# LED_s_Valvulas.net
KiCad netlist of a schematic drawn in Altium Designer
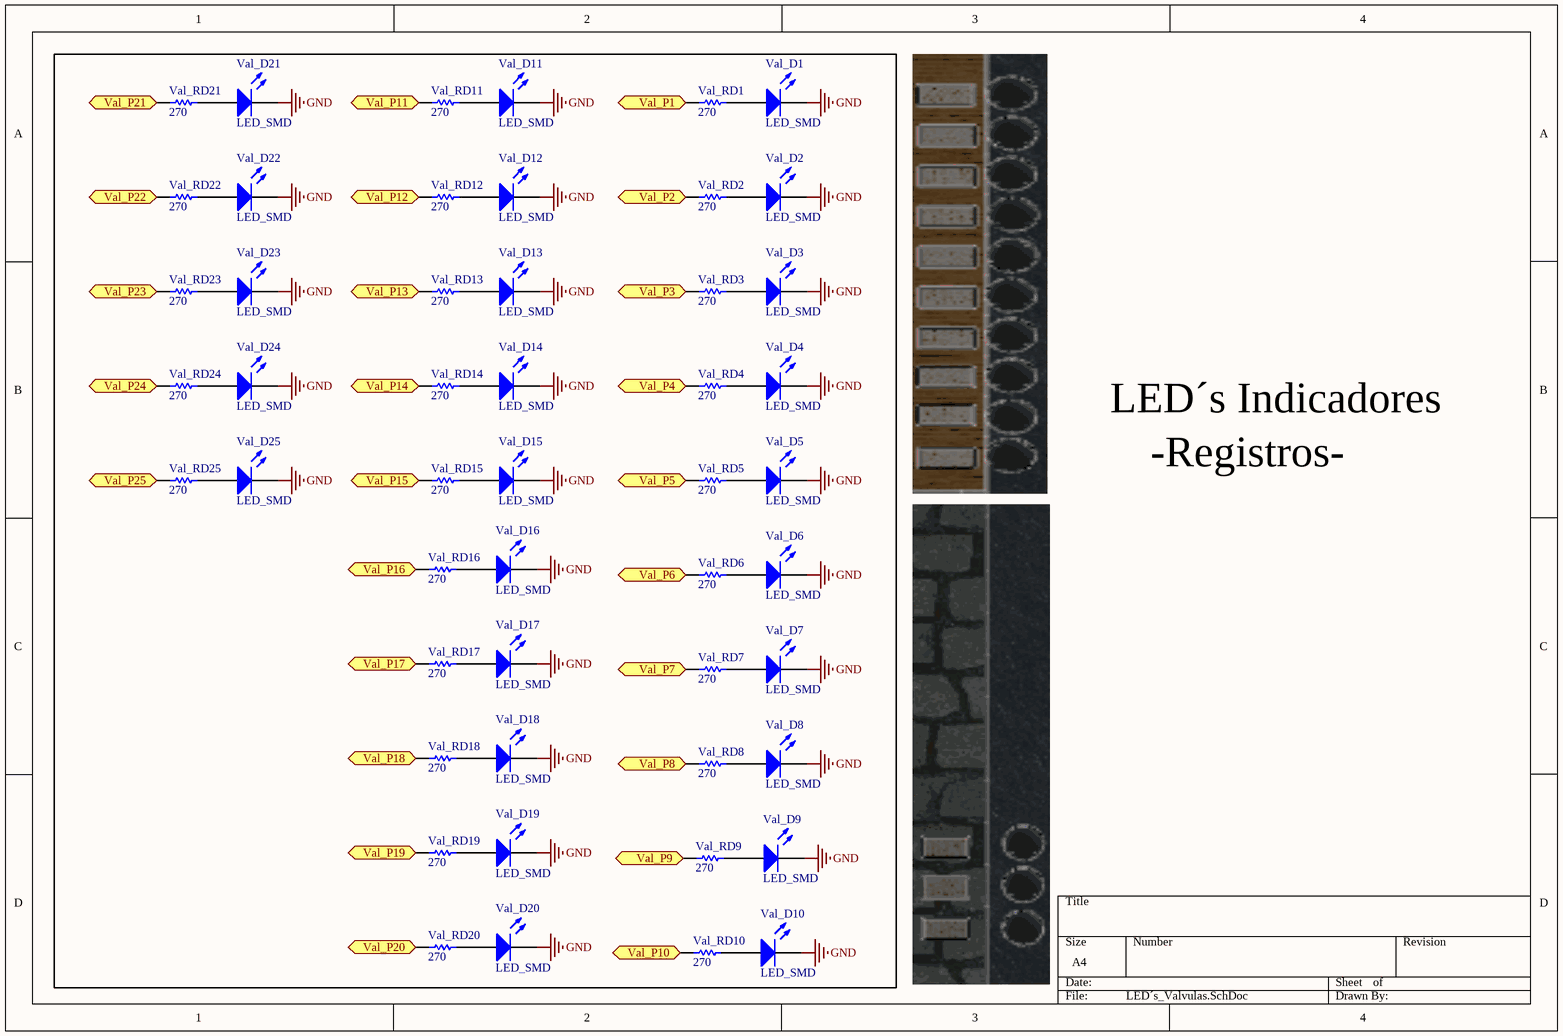
[diagram p0: LED´s_Valvulas.SchDoc]

(export (version "E")
  (design (tool "Eeschema 10.0.6"))
  (components
    (comp (ref "Val_D1")
      (value "LED_SMD")
      (footprint "0805")
      (description "LED SMD")
      (fields (field (name "PUBLISHER") "Altium Limited"))
      (libsource (lib "Libreria_Organo") (part "LED_SMD"))
    )
    (comp (ref "Val_D2")
      (value "LED_SMD")
      (footprint "0805")
      (description "LED SMD")
      (fields (field (name "PUBLISHER") "Altium Limited"))
      (libsource (lib "Libreria_Organo") (part "LED_SMD"))
    )
    (comp (ref "Val_D3")
      (value "LED_SMD")
      (footprint "0805")
      (description "LED SMD")
      (fields (field (name "PUBLISHER") "Altium Limited"))
      (libsource (lib "Libreria_Organo") (part "LED_SMD"))
    )
    (comp (ref "Val_D4")
      (value "LED_SMD")
      (footprint "0805")
      (description "LED SMD")
      (fields (field (name "PUBLISHER") "Altium Limited"))
      (libsource (lib "Libreria_Organo") (part "LED_SMD"))
    )
    (comp (ref "Val_D5")
      (value "LED_SMD")
      (footprint "0805")
      (description "LED SMD")
      (fields (field (name "PUBLISHER") "Altium Limited"))
      (libsource (lib "Libreria_Organo") (part "LED_SMD"))
    )
    (comp (ref "Val_D6")
      (value "LED_SMD")
      (footprint "0805")
      (description "LED SMD")
      (fields (field (name "PUBLISHER") "Altium Limited"))
      (libsource (lib "Libreria_Organo") (part "LED_SMD"))
    )
    (comp (ref "Val_D7")
      (value "LED_SMD")
      (footprint "0805")
      (description "LED SMD")
      (fields (field (name "PUBLISHER") "Altium Limited"))
      (libsource (lib "Libreria_Organo") (part "LED_SMD"))
    )
    (comp (ref "Val_D8")
      (value "LED_SMD")
      (footprint "0805")
      (description "LED SMD")
      (fields (field (name "PUBLISHER") "Altium Limited"))
      (libsource (lib "Libreria_Organo") (part "LED_SMD"))
    )
    (comp (ref "Val_D9")
      (value "LED_SMD")
      (footprint "0805")
      (description "LED SMD")
      (fields (field (name "PUBLISHER") "Altium Limited"))
      (libsource (lib "Libreria_Organo") (part "LED_SMD"))
    )
    (comp (ref "Val_D10")
      (value "LED_SMD")
      (footprint "0805")
      (description "LED SMD")
      (fields (field (name "PUBLISHER") "Altium Limited"))
      (libsource (lib "Libreria_Organo") (part "LED_SMD"))
    )
    (comp (ref "Val_D11")
      (value "LED_SMD")
      (footprint "0805")
      (description "LED SMD")
      (fields (field (name "PUBLISHER") "Altium Limited"))
      (libsource (lib "Libreria_Organo") (part "LED_SMD"))
    )
    (comp (ref "Val_D12")
      (value "LED_SMD")
      (footprint "0805")
      (description "LED SMD")
      (fields (field (name "PUBLISHER") "Altium Limited"))
      (libsource (lib "Libreria_Organo") (part "LED_SMD"))
    )
    (comp (ref "Val_D13")
      (value "LED_SMD")
      (footprint "0805")
      (description "LED SMD")
      (fields (field (name "PUBLISHER") "Altium Limited"))
      (libsource (lib "Libreria_Organo") (part "LED_SMD"))
    )
    (comp (ref "Val_D14")
      (value "LED_SMD")
      (footprint "0805")
      (description "LED SMD")
      (fields (field (name "PUBLISHER") "Altium Limited"))
      (libsource (lib "Libreria_Organo") (part "LED_SMD"))
    )
    (comp (ref "Val_D15")
      (value "LED_SMD")
      (footprint "0805")
      (description "LED SMD")
      (fields (field (name "PUBLISHER") "Altium Limited"))
      (libsource (lib "Libreria_Organo") (part "LED_SMD"))
    )
    (comp (ref "Val_D16")
      (value "LED_SMD")
      (footprint "0805")
      (description "LED SMD")
      (fields (field (name "PUBLISHER") "Altium Limited"))
      (libsource (lib "Libreria_Organo") (part "LED_SMD"))
    )
    (comp (ref "Val_D17")
      (value "LED_SMD")
      (footprint "0805")
      (description "LED SMD")
      (fields (field (name "PUBLISHER") "Altium Limited"))
      (libsource (lib "Libreria_Organo") (part "LED_SMD"))
    )
    (comp (ref "Val_D18")
      (value "LED_SMD")
      (footprint "0805")
      (description "LED SMD")
      (fields (field (name "PUBLISHER") "Altium Limited"))
      (libsource (lib "Libreria_Organo") (part "LED_SMD"))
    )
    (comp (ref "Val_D19")
      (value "LED_SMD")
      (footprint "0805")
      (description "LED SMD")
      (fields (field (name "PUBLISHER") "Altium Limited"))
      (libsource (lib "Libreria_Organo") (part "LED_SMD"))
    )
    (comp (ref "Val_D20")
      (value "LED_SMD")
      (footprint "0805")
      (description "LED SMD")
      (fields (field (name "PUBLISHER") "Altium Limited"))
      (libsource (lib "Libreria_Organo") (part "LED_SMD"))
    )
    (comp (ref "Val_D21")
      (value "LED_SMD")
      (footprint "0805")
      (description "LED SMD")
      (fields (field (name "PUBLISHER") "Altium Limited"))
      (libsource (lib "Libreria_Organo") (part "LED_SMD"))
    )
    (comp (ref "Val_D22")
      (value "LED_SMD")
      (footprint "0805")
      (description "LED SMD")
      (fields (field (name "PUBLISHER") "Altium Limited"))
      (libsource (lib "Libreria_Organo") (part "LED_SMD"))
    )
    (comp (ref "Val_D23")
      (value "LED_SMD")
      (footprint "0805")
      (description "LED SMD")
      (fields (field (name "PUBLISHER") "Altium Limited"))
      (libsource (lib "Libreria_Organo") (part "LED_SMD"))
    )
    (comp (ref "Val_D24")
      (value "LED_SMD")
      (footprint "0805")
      (description "LED SMD")
      (fields (field (name "PUBLISHER") "Altium Limited"))
      (libsource (lib "Libreria_Organo") (part "LED_SMD"))
    )
    (comp (ref "Val_D25")
      (value "LED_SMD")
      (footprint "0805")
      (description "LED SMD")
      (fields (field (name "PUBLISHER") "Altium Limited"))
      (libsource (lib "Libreria_Organo") (part "LED_SMD"))
    )
    (comp (ref "Val_RD1")
      (value "270")
      (footprint "0805 Chip Res")
      (description "Res Chip 0805")
      (fields (field (name "PUBLISHER") "Altium Limited"))
      (libsource (lib "Libreria_Organo") (part "Resistencia"))
    )
    (comp (ref "Val_RD2")
      (value "270")
      (footprint "0805 Chip Res")
      (description "Res Chip 0805")
      (fields (field (name "PUBLISHER") "Altium Limited"))
      (libsource (lib "Libreria_Organo") (part "Resistencia"))
    )
    (comp (ref "Val_RD3")
      (value "270")
      (footprint "0805 Chip Res")
      (description "Res Chip 0805")
      (fields (field (name "PUBLISHER") "Altium Limited"))
      (libsource (lib "Libreria_Organo") (part "Resistencia"))
    )
    (comp (ref "Val_RD4")
      (value "270")
      (footprint "0805 Chip Res")
      (description "Res Chip 0805")
      (fields (field (name "PUBLISHER") "Altium Limited"))
      (libsource (lib "Libreria_Organo") (part "Resistencia"))
    )
    (comp (ref "Val_RD5")
      (value "270")
      (footprint "0805 Chip Res")
      (description "Res Chip 0805")
      (fields (field (name "PUBLISHER") "Altium Limited"))
      (libsource (lib "Libreria_Organo") (part "Resistencia"))
    )
    (comp (ref "Val_RD6")
      (value "270")
      (footprint "0805 Chip Res")
      (description "Res Chip 0805")
      (fields (field (name "PUBLISHER") "Altium Limited"))
      (libsource (lib "Libreria_Organo") (part "Resistencia"))
    )
    (comp (ref "Val_RD7")
      (value "270")
      (footprint "0805 Chip Res")
      (description "Res Chip 0805")
      (fields (field (name "PUBLISHER") "Altium Limited"))
      (libsource (lib "Libreria_Organo") (part "Resistencia"))
    )
    (comp (ref "Val_RD8")
      (value "270")
      (footprint "0805 Chip Res")
      (description "Res Chip 0805")
      (fields (field (name "PUBLISHER") "Altium Limited"))
      (libsource (lib "Libreria_Organo") (part "Resistencia"))
    )
    (comp (ref "Val_RD9")
      (value "270")
      (footprint "0805 Chip Res")
      (description "Res Chip 0805")
      (fields (field (name "PUBLISHER") "Altium Limited"))
      (libsource (lib "Libreria_Organo") (part "Resistencia"))
    )
    (comp (ref "Val_RD10")
      (value "270")
      (footprint "0805 Chip Res")
      (description "Res Chip 0805")
      (fields (field (name "PUBLISHER") "Altium Limited"))
      (libsource (lib "Libreria_Organo") (part "Resistencia"))
    )
    (comp (ref "Val_RD11")
      (value "270")
      (footprint "0805 Chip Res")
      (description "Res Chip 0805")
      (fields (field (name "PUBLISHER") "Altium Limited"))
      (libsource (lib "Libreria_Organo") (part "Resistencia"))
    )
    (comp (ref "Val_RD12")
      (value "270")
      (footprint "0805 Chip Res")
      (description "Res Chip 0805")
      (fields (field (name "PUBLISHER") "Altium Limited"))
      (libsource (lib "Libreria_Organo") (part "Resistencia"))
    )
    (comp (ref "Val_RD13")
      (value "270")
      (footprint "0805 Chip Res")
      (description "Res Chip 0805")
      (fields (field (name "PUBLISHER") "Altium Limited"))
      (libsource (lib "Libreria_Organo") (part "Resistencia"))
    )
    (comp (ref "Val_RD14")
      (value "270")
      (footprint "0805 Chip Res")
      (description "Res Chip 0805")
      (fields (field (name "PUBLISHER") "Altium Limited"))
      (libsource (lib "Libreria_Organo") (part "Resistencia"))
    )
    (comp (ref "Val_RD15")
      (value "270")
      (footprint "0805 Chip Res")
      (description "Res Chip 0805")
      (fields (field (name "PUBLISHER") "Altium Limited"))
      (libsource (lib "Libreria_Organo") (part "Resistencia"))
    )
    (comp (ref "Val_RD16")
      (value "270")
      (footprint "0805 Chip Res")
      (description "Res Chip 0805")
      (fields (field (name "PUBLISHER") "Altium Limited"))
      (libsource (lib "Libreria_Organo") (part "Resistencia"))
    )
    (comp (ref "Val_RD17")
      (value "270")
      (footprint "0805 Chip Res")
      (description "Res Chip 0805")
      (fields (field (name "PUBLISHER") "Altium Limited"))
      (libsource (lib "Libreria_Organo") (part "Resistencia"))
    )
    (comp (ref "Val_RD18")
      (value "270")
      (footprint "0805 Chip Res")
      (description "Res Chip 0805")
      (fields (field (name "PUBLISHER") "Altium Limited"))
      (libsource (lib "Libreria_Organo") (part "Resistencia"))
    )
    (comp (ref "Val_RD19")
      (value "270")
      (footprint "0805 Chip Res")
      (description "Res Chip 0805")
      (fields (field (name "PUBLISHER") "Altium Limited"))
      (libsource (lib "Libreria_Organo") (part "Resistencia"))
    )
    (comp (ref "Val_RD20")
      (value "270")
      (footprint "0805 Chip Res")
      (description "Res Chip 0805")
      (fields (field (name "PUBLISHER") "Altium Limited"))
      (libsource (lib "Libreria_Organo") (part "Resistencia"))
    )
    (comp (ref "Val_RD21")
      (value "270")
      (footprint "0805 Chip Res")
      (description "Res Chip 0805")
      (fields (field (name "PUBLISHER") "Altium Limited"))
      (libsource (lib "Libreria_Organo") (part "Resistencia"))
    )
    (comp (ref "Val_RD22")
      (value "270")
      (footprint "0805 Chip Res")
      (description "Res Chip 0805")
      (fields (field (name "PUBLISHER") "Altium Limited"))
      (libsource (lib "Libreria_Organo") (part "Resistencia"))
    )
    (comp (ref "Val_RD23")
      (value "270")
      (footprint "0805 Chip Res")
      (description "Res Chip 0805")
      (fields (field (name "PUBLISHER") "Altium Limited"))
      (libsource (lib "Libreria_Organo") (part "Resistencia"))
    )
    (comp (ref "Val_RD24")
      (value "270")
      (footprint "0805 Chip Res")
      (description "Res Chip 0805")
      (fields (field (name "PUBLISHER") "Altium Limited"))
      (libsource (lib "Libreria_Organo") (part "Resistencia"))
    )
    (comp (ref "Val_RD25")
      (value "270")
      (footprint "0805 Chip Res")
      (description "Res Chip 0805")
      (fields (field (name "PUBLISHER") "Altium Limited"))
      (libsource (lib "Libreria_Organo") (part "Resistencia"))
    )
  )
  (nets
    (net (code "1") (name "/Val_P1") (class "Default")
      (node (ref "Val_RD1") (pin "1") (pinfunction "1_1") (pintype "passive"))
    )
    (net (code "2") (name "/Val_P2") (class "Default")
      (node (ref "Val_RD2") (pin "1") (pinfunction "1_1") (pintype "passive"))
    )
    (net (code "3") (name "/Val_P3") (class "Default")
      (node (ref "Val_RD3") (pin "1") (pinfunction "1_1") (pintype "passive"))
    )
    (net (code "4") (name "/Val_P4") (class "Default")
      (node (ref "Val_RD4") (pin "1") (pinfunction "1_1") (pintype "passive"))
    )
    (net (code "5") (name "/Val_P5") (class "Default")
      (node (ref "Val_RD5") (pin "1") (pinfunction "1_1") (pintype "passive"))
    )
    (net (code "6") (name "/Val_P6") (class "Default")
      (node (ref "Val_RD6") (pin "1") (pinfunction "1_1") (pintype "passive"))
    )
    (net (code "7") (name "/Val_P7") (class "Default")
      (node (ref "Val_RD7") (pin "1") (pinfunction "1_1") (pintype "passive"))
    )
    (net (code "8") (name "/Val_P8") (class "Default")
      (node (ref "Val_RD8") (pin "1") (pinfunction "1_1") (pintype "passive"))
    )
    (net (code "9") (name "/Val_P9") (class "Default")
      (node (ref "Val_RD9") (pin "1") (pinfunction "1_1") (pintype "passive"))
    )
    (net (code "10") (name "/Val_P10") (class "Default")
      (node (ref "Val_RD10") (pin "1") (pinfunction "1_1") (pintype "passive"))
    )
    (net (code "11") (name "/Val_P11") (class "Default")
      (node (ref "Val_RD11") (pin "1") (pinfunction "1_1") (pintype "passive"))
    )
    (net (code "12") (name "/Val_P12") (class "Default")
      (node (ref "Val_RD12") (pin "1") (pinfunction "1_1") (pintype "passive"))
    )
    (net (code "13") (name "/Val_P13") (class "Default")
      (node (ref "Val_RD13") (pin "1") (pinfunction "1_1") (pintype "passive"))
    )
    (net (code "14") (name "/Val_P14") (class "Default")
      (node (ref "Val_RD14") (pin "1") (pinfunction "1_1") (pintype "passive"))
    )
    (net (code "15") (name "/Val_P15") (class "Default")
      (node (ref "Val_RD15") (pin "1") (pinfunction "1_1") (pintype "passive"))
    )
    (net (code "16") (name "/Val_P16") (class "Default")
      (node (ref "Val_RD16") (pin "1") (pinfunction "1_1") (pintype "passive"))
    )
    (net (code "17") (name "/Val_P17") (class "Default")
      (node (ref "Val_RD17") (pin "1") (pinfunction "1_1") (pintype "passive"))
    )
    (net (code "18") (name "/Val_P18") (class "Default")
      (node (ref "Val_RD18") (pin "1") (pinfunction "1_1") (pintype "passive"))
    )
    (net (code "19") (name "/Val_P19") (class "Default")
      (node (ref "Val_RD19") (pin "1") (pinfunction "1_1") (pintype "passive"))
    )
    (net (code "20") (name "/Val_P20") (class "Default")
      (node (ref "Val_RD20") (pin "1") (pinfunction "1_1") (pintype "passive"))
    )
    (net (code "21") (name "/Val_P21") (class "Default")
      (node (ref "Val_RD21") (pin "1") (pinfunction "1_1") (pintype "passive"))
    )
    (net (code "22") (name "/Val_P22") (class "Default")
      (node (ref "Val_RD22") (pin "1") (pinfunction "1_1") (pintype "passive"))
    )
    (net (code "23") (name "/Val_P23") (class "Default")
      (node (ref "Val_RD23") (pin "1") (pinfunction "1_1") (pintype "passive"))
    )
    (net (code "24") (name "/Val_P24") (class "Default")
      (node (ref "Val_RD24") (pin "1") (pinfunction "1_1") (pintype "passive"))
    )
    (net (code "25") (name "/Val_P25") (class "Default")
      (node (ref "Val_RD25") (pin "1") (pinfunction "1_1") (pintype "passive"))
    )
    (net (code "26") (name "GND") (class "Default")
      (node (ref "Val_D1") (pin "2") (pinfunction "K_2") (pintype "passive"))
      (node (ref "Val_D10") (pin "2") (pinfunction "K_2") (pintype "passive"))
      (node (ref "Val_D11") (pin "2") (pinfunction "K_2") (pintype "passive"))
      (node (ref "Val_D12") (pin "2") (pinfunction "K_2") (pintype "passive"))
      (node (ref "Val_D13") (pin "2") (pinfunction "K_2") (pintype "passive"))
      (node (ref "Val_D14") (pin "2") (pinfunction "K_2") (pintype "passive"))
      (node (ref "Val_D15") (pin "2") (pinfunction "K_2") (pintype "passive"))
      (node (ref "Val_D16") (pin "2") (pinfunction "K_2") (pintype "passive"))
      (node (ref "Val_D17") (pin "2") (pinfunction "K_2") (pintype "passive"))
      (node (ref "Val_D18") (pin "2") (pinfunction "K_2") (pintype "passive"))
      (node (ref "Val_D19") (pin "2") (pinfunction "K_2") (pintype "passive"))
      (node (ref "Val_D2") (pin "2") (pinfunction "K_2") (pintype "passive"))
      (node (ref "Val_D20") (pin "2") (pinfunction "K_2") (pintype "passive"))
      (node (ref "Val_D21") (pin "2") (pinfunction "K_2") (pintype "passive"))
      (node (ref "Val_D22") (pin "2") (pinfunction "K_2") (pintype "passive"))
      (node (ref "Val_D23") (pin "2") (pinfunction "K_2") (pintype "passive"))
      (node (ref "Val_D24") (pin "2") (pinfunction "K_2") (pintype "passive"))
      (node (ref "Val_D25") (pin "2") (pinfunction "K_2") (pintype "passive"))
      (node (ref "Val_D3") (pin "2") (pinfunction "K_2") (pintype "passive"))
      (node (ref "Val_D4") (pin "2") (pinfunction "K_2") (pintype "passive"))
      (node (ref "Val_D5") (pin "2") (pinfunction "K_2") (pintype "passive"))
      (node (ref "Val_D6") (pin "2") (pinfunction "K_2") (pintype "passive"))
      (node (ref "Val_D7") (pin "2") (pinfunction "K_2") (pintype "passive"))
      (node (ref "Val_D8") (pin "2") (pinfunction "K_2") (pintype "passive"))
      (node (ref "Val_D9") (pin "2") (pinfunction "K_2") (pintype "passive"))
    )
    (net (code "27") (name "Net-(Val_D1-A)") (class "Default")
      (node (ref "Val_D1") (pin "1") (pinfunction "A_1") (pintype "passive"))
      (node (ref "Val_RD1") (pin "2") (pinfunction "2_2") (pintype "passive"))
    )
    (net (code "28") (name "Net-(Val_D2-A)") (class "Default")
      (node (ref "Val_D2") (pin "1") (pinfunction "A_1") (pintype "passive"))
      (node (ref "Val_RD2") (pin "2") (pinfunction "2_2") (pintype "passive"))
    )
    (net (code "29") (name "Net-(Val_D3-A)") (class "Default")
      (node (ref "Val_D3") (pin "1") (pinfunction "A_1") (pintype "passive"))
      (node (ref "Val_RD3") (pin "2") (pinfunction "2_2") (pintype "passive"))
    )
    (net (code "30") (name "Net-(Val_D4-A)") (class "Default")
      (node (ref "Val_D4") (pin "1") (pinfunction "A_1") (pintype "passive"))
      (node (ref "Val_RD4") (pin "2") (pinfunction "2_2") (pintype "passive"))
    )
    (net (code "31") (name "Net-(Val_D5-A)") (class "Default")
      (node (ref "Val_D5") (pin "1") (pinfunction "A_1") (pintype "passive"))
      (node (ref "Val_RD5") (pin "2") (pinfunction "2_2") (pintype "passive"))
    )
    (net (code "32") (name "Net-(Val_D6-A)") (class "Default")
      (node (ref "Val_D6") (pin "1") (pinfunction "A_1") (pintype "passive"))
      (node (ref "Val_RD6") (pin "2") (pinfunction "2_2") (pintype "passive"))
    )
    (net (code "33") (name "Net-(Val_D7-A)") (class "Default")
      (node (ref "Val_D7") (pin "1") (pinfunction "A_1") (pintype "passive"))
      (node (ref "Val_RD7") (pin "2") (pinfunction "2_2") (pintype "passive"))
    )
    (net (code "34") (name "Net-(Val_D8-A)") (class "Default")
      (node (ref "Val_D8") (pin "1") (pinfunction "A_1") (pintype "passive"))
      (node (ref "Val_RD8") (pin "2") (pinfunction "2_2") (pintype "passive"))
    )
    (net (code "35") (name "Net-(Val_D9-A)") (class "Default")
      (node (ref "Val_D9") (pin "1") (pinfunction "A_1") (pintype "passive"))
      (node (ref "Val_RD9") (pin "2") (pinfunction "2_2") (pintype "passive"))
    )
    (net (code "36") (name "Net-(Val_D10-A)") (class "Default")
      (node (ref "Val_D10") (pin "1") (pinfunction "A_1") (pintype "passive"))
      (node (ref "Val_RD10") (pin "2") (pinfunction "2_2") (pintype "passive"))
    )
    (net (code "37") (name "Net-(Val_D11-A)") (class "Default")
      (node (ref "Val_D11") (pin "1") (pinfunction "A_1") (pintype "passive"))
      (node (ref "Val_RD11") (pin "2") (pinfunction "2_2") (pintype "passive"))
    )
    (net (code "38") (name "Net-(Val_D12-A)") (class "Default")
      (node (ref "Val_D12") (pin "1") (pinfunction "A_1") (pintype "passive"))
      (node (ref "Val_RD12") (pin "2") (pinfunction "2_2") (pintype "passive"))
    )
    (net (code "39") (name "Net-(Val_D13-A)") (class "Default")
      (node (ref "Val_D13") (pin "1") (pinfunction "A_1") (pintype "passive"))
      (node (ref "Val_RD13") (pin "2") (pinfunction "2_2") (pintype "passive"))
    )
    (net (code "40") (name "Net-(Val_D14-A)") (class "Default")
      (node (ref "Val_D14") (pin "1") (pinfunction "A_1") (pintype "passive"))
      (node (ref "Val_RD14") (pin "2") (pinfunction "2_2") (pintype "passive"))
    )
    (net (code "41") (name "Net-(Val_D15-A)") (class "Default")
      (node (ref "Val_D15") (pin "1") (pinfunction "A_1") (pintype "passive"))
      (node (ref "Val_RD15") (pin "2") (pinfunction "2_2") (pintype "passive"))
    )
    (net (code "42") (name "Net-(Val_D16-A)") (class "Default")
      (node (ref "Val_D16") (pin "1") (pinfunction "A_1") (pintype "passive"))
      (node (ref "Val_RD16") (pin "2") (pinfunction "2_2") (pintype "passive"))
    )
    (net (code "43") (name "Net-(Val_D17-A)") (class "Default")
      (node (ref "Val_D17") (pin "1") (pinfunction "A_1") (pintype "passive"))
      (node (ref "Val_RD17") (pin "2") (pinfunction "2_2") (pintype "passive"))
    )
    (net (code "44") (name "Net-(Val_D18-A)") (class "Default")
      (node (ref "Val_D18") (pin "1") (pinfunction "A_1") (pintype "passive"))
      (node (ref "Val_RD18") (pin "2") (pinfunction "2_2") (pintype "passive"))
    )
    (net (code "45") (name "Net-(Val_D19-A)") (class "Default")
      (node (ref "Val_D19") (pin "1") (pinfunction "A_1") (pintype "passive"))
      (node (ref "Val_RD19") (pin "2") (pinfunction "2_2") (pintype "passive"))
    )
    (net (code "46") (name "Net-(Val_D20-A)") (class "Default")
      (node (ref "Val_D20") (pin "1") (pinfunction "A_1") (pintype "passive"))
      (node (ref "Val_RD20") (pin "2") (pinfunction "2_2") (pintype "passive"))
    )
    (net (code "47") (name "Net-(Val_D21-A)") (class "Default")
      (node (ref "Val_D21") (pin "1") (pinfunction "A_1") (pintype "passive"))
      (node (ref "Val_RD21") (pin "2") (pinfunction "2_2") (pintype "passive"))
    )
    (net (code "48") (name "Net-(Val_D22-A)") (class "Default")
      (node (ref "Val_D22") (pin "1") (pinfunction "A_1") (pintype "passive"))
      (node (ref "Val_RD22") (pin "2") (pinfunction "2_2") (pintype "passive"))
    )
    (net (code "49") (name "Net-(Val_D23-A)") (class "Default")
      (node (ref "Val_D23") (pin "1") (pinfunction "A_1") (pintype "passive"))
      (node (ref "Val_RD23") (pin "2") (pinfunction "2_2") (pintype "passive"))
    )
    (net (code "50") (name "Net-(Val_D24-A)") (class "Default")
      (node (ref "Val_D24") (pin "1") (pinfunction "A_1") (pintype "passive"))
      (node (ref "Val_RD24") (pin "2") (pinfunction "2_2") (pintype "passive"))
    )
    (net (code "51") (name "Net-(Val_D25-A)") (class "Default")
      (node (ref "Val_D25") (pin "1") (pinfunction "A_1") (pintype "passive"))
      (node (ref "Val_RD25") (pin "2") (pinfunction "2_2") (pintype "passive"))
    )
  )
)
